# uradmonitor_D_100_61.net
KiCad netlist of a schematic drawn in EAGLE
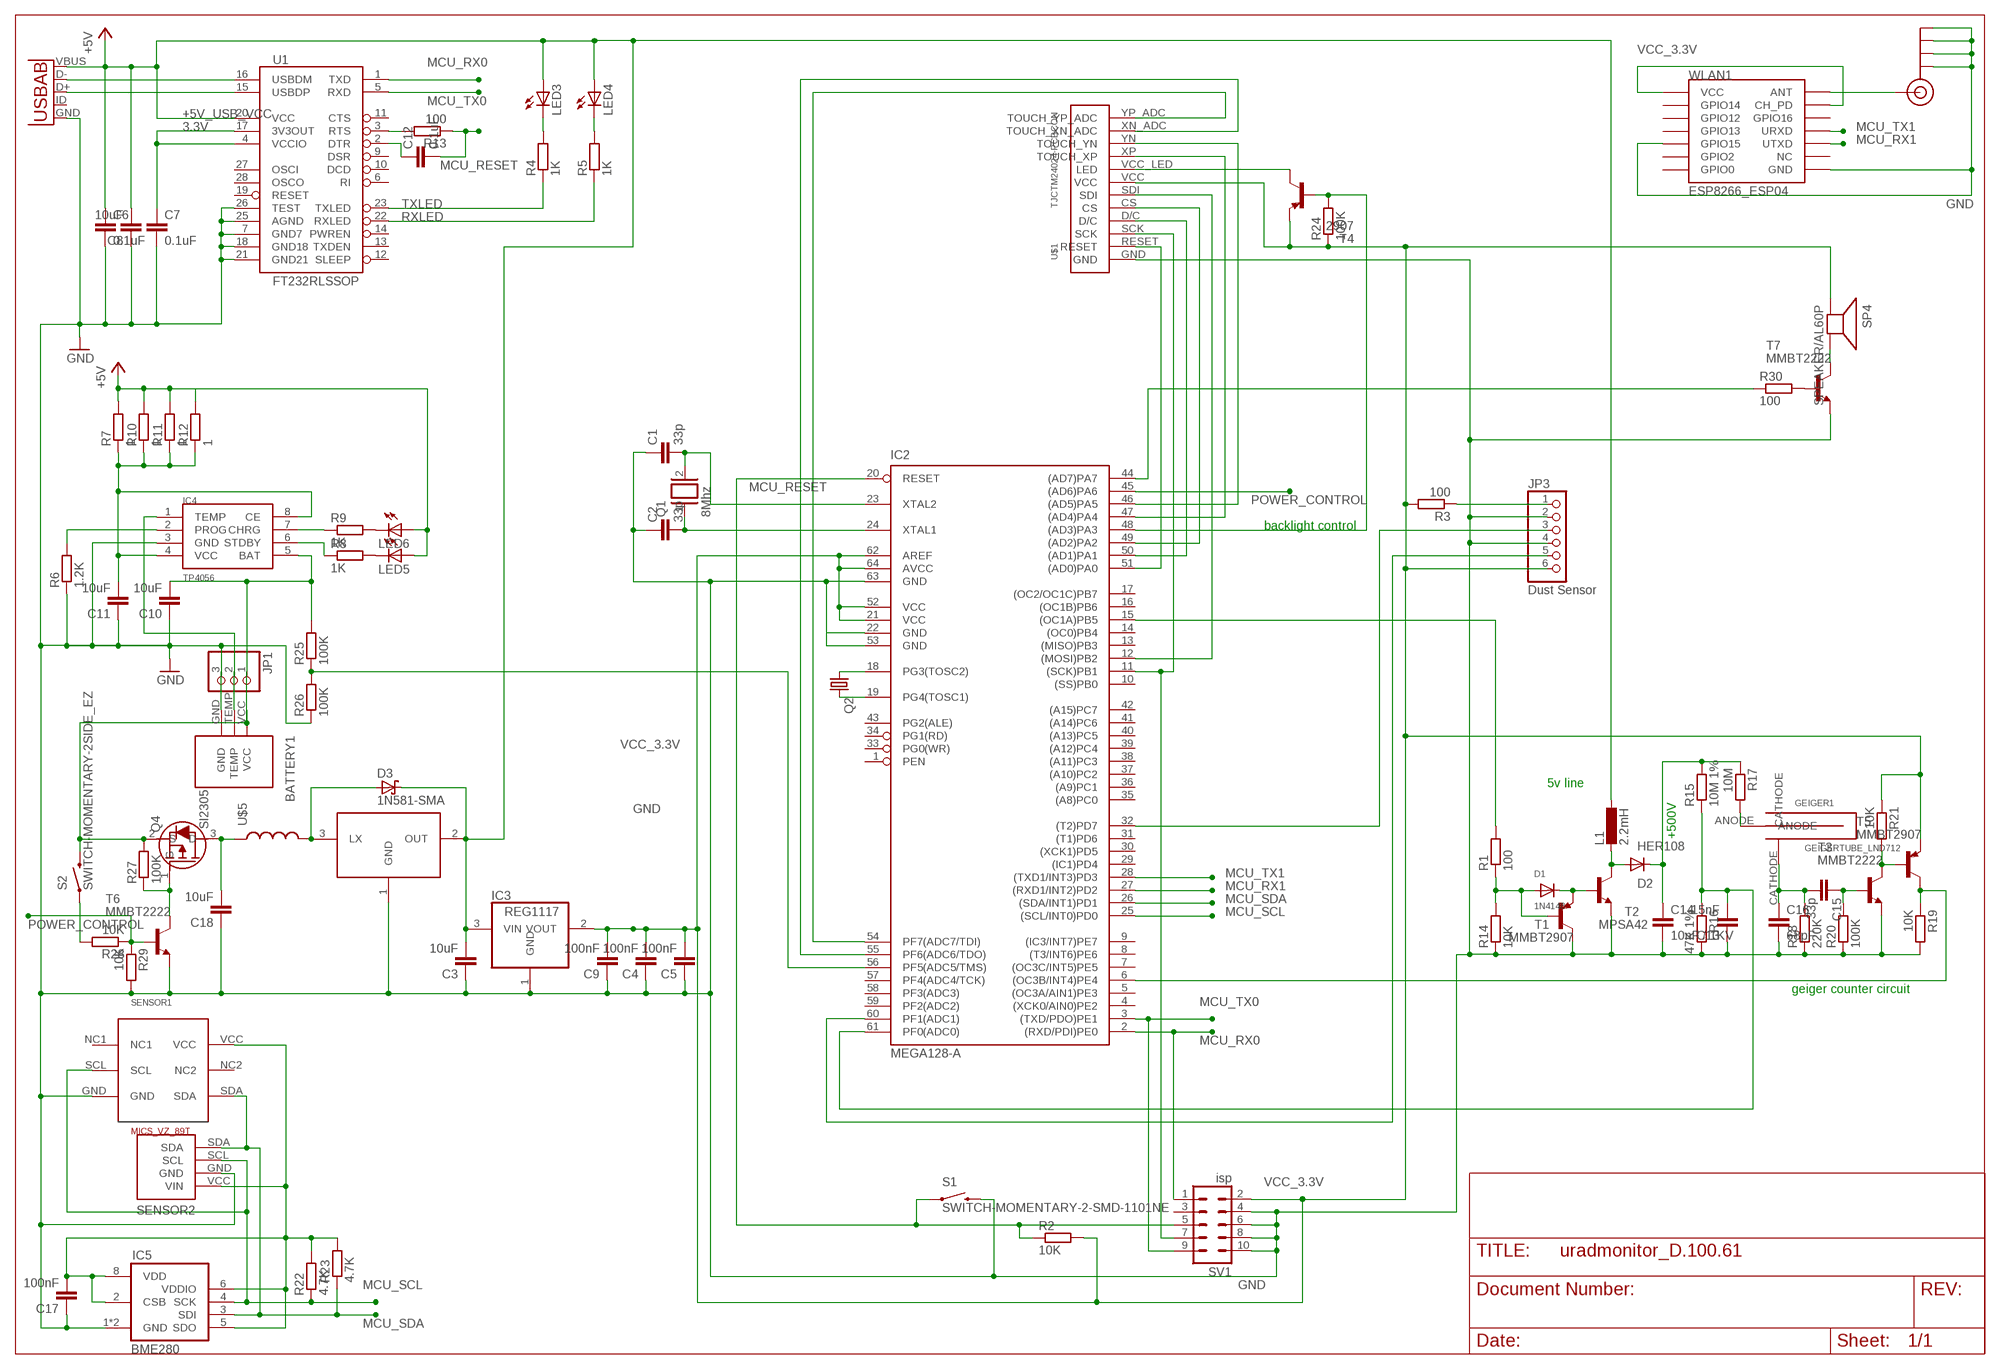
[diagram p0: schematic, sheet 1]

(export (version "E")
  (design (tool "Eeschema 10.0.6"))
  (components
    (comp (ref "BATTERY1")
      (value "BAT-CASIO-NP40BATTERY")
      (footprint "eagle-import:BAT-CASIO-NP40")
      (libsource (lib "eagle-import") (part "BAT-CASIO-NP40BATTERY"))
    )
    (comp (ref "C1")
      (value "33p")
      (footprint "eagle-import:C0805K")
      (libsource (lib "eagle-import") (part "C-EUC0805K"))
    )
    (comp (ref "C2")
      (value "33p")
      (footprint "eagle-import:C0805K")
      (libsource (lib "eagle-import") (part "C-EUC0805K"))
    )
    (comp (ref "C3")
      (value "10uF")
      (footprint "eagle-import:C0805K")
      (libsource (lib "eagle-import") (part "C-EUC0805K"))
    )
    (comp (ref "C4")
      (value "100nF")
      (footprint "eagle-import:C0805K")
      (libsource (lib "eagle-import") (part "C-EUC0805K"))
    )
    (comp (ref "C5")
      (value "100nF")
      (footprint "eagle-import:C0805K")
      (libsource (lib "eagle-import") (part "C-EUC0805K"))
    )
    (comp (ref "C6")
      (value "0.1uF")
      (footprint "eagle-import:0805")
      (libsource (lib "eagle-import") (part "CAP0805"))
    )
    (comp (ref "C7")
      (value "0.1uF")
      (footprint "eagle-import:0805")
      (libsource (lib "eagle-import") (part "CAP0805"))
    )
    (comp (ref "C8")
      (value "10uF")
      (footprint "eagle-import:C0805K")
      (libsource (lib "eagle-import") (part "C-EUC0805K"))
    )
    (comp (ref "C9")
      (value "100nF")
      (footprint "eagle-import:C0805K")
      (libsource (lib "eagle-import") (part "C-EUC0805K"))
    )
    (comp (ref "C10")
      (value "10uF")
      (footprint "eagle-import:C0805K")
      (libsource (lib "eagle-import") (part "C-EUC0805K"))
    )
    (comp (ref "C11")
      (value "10uF")
      (footprint "eagle-import:C0805K")
      (libsource (lib "eagle-import") (part "C-EUC0805K"))
    )
    (comp (ref "C12")
      (value "0.1uF")
      (footprint "eagle-import:0805")
      (libsource (lib "eagle-import") (part "CAP0805"))
    )
    (comp (ref "C13")
      (value "15nF")
      (footprint "eagle-import:C0805K")
      (libsource (lib "eagle-import") (part "C-EUC0805K"))
    )
    (comp (ref "C14")
      (value "10nF / 1KV")
      (footprint "eagle-import:C050-025X075")
      (libsource (lib "eagle-import") (part "C-EU050-025X075"))
    )
    (comp (ref "C15")
      (value "33p")
      (footprint "eagle-import:C0805K")
      (libsource (lib "eagle-import") (part "C-EUC0805K"))
    )
    (comp (ref "C16")
      (value "68pF")
      (footprint "eagle-import:C0805K")
      (libsource (lib "eagle-import") (part "C-EUC0805K"))
    )
    (comp (ref "C17")
      (value "100nF")
      (footprint "eagle-import:C0805K")
      (libsource (lib "eagle-import") (part "C-EUC0805K"))
    )
    (comp (ref "C18")
      (value "10uF")
      (footprint "eagle-import:C0805K")
      (libsource (lib "eagle-import") (part "C-EUC0805K"))
    )
    (comp (ref "D1")
      (value "1N4148")
      (footprint "eagle-import:SOD-323F")
      (libsource (lib "eagle-import") (part "DIODESOD-323F"))
    )
    (comp (ref "D2")
      (value "HER108")
      (footprint "eagle-import:DO-214AC")
      (libsource (lib "eagle-import") (part "DIODE-DO-214AC"))
    )
    (comp (ref "D3")
      (value "1N581-SMA")
      (footprint "eagle-import:SMA-DIODE")
      (libsource (lib "eagle-import") (part "1N581-SMA"))
    )
    (comp (ref "GEIGER1")
      (value "GEIGERTUBE_LND712")
      (footprint "eagle-import:GEIGERTUBE_LND712")
      (libsource (lib "eagle-import") (part "GEIGERTUBE_LND712"))
    )
    (comp (ref "IC2")
      (value "MEGA128-A")
      (footprint "eagle-import:TQFP64")
      (fields (field (name "MPN") "ATMEGA128-16AU"))
      (libsource (lib "eagle-import") (part "MEGA128-A"))
    )
    (comp (ref "IC3")
      (value "REG1117")
      (footprint "eagle-import:SOT223")
      (libsource (lib "eagle-import") (part "REG1117"))
    )
    (comp (ref "IC4")
      (value "TP4056")
      (footprint "eagle-import:TP4056")
      (libsource (lib "eagle-import") (part "TP4056"))
    )
    (comp (ref "IC5")
      (value "BME280")
      (footprint "eagle-import:BME280")
      (libsource (lib "eagle-import") (part "BME280"))
    )
    (comp (ref "J$1")
      (value "SMA_EDGE")
      (footprint "eagle-import:SMA-EDGE")
      (libsource (lib "eagle-import") (part "SMA_EDGE"))
    )
    (comp (ref "JP1")
      (value "PINHD-1X3")
      (footprint "eagle-import:1X03")
      (libsource (lib "eagle-import") (part "PINHD-1X3"))
    )
    (comp (ref "JP3")
      (value "Dust Sensor")
      (footprint "eagle-import:1X06-CLEANBIG")
      (libsource (lib "eagle-import") (part "PINHD-1X6CB"))
    )
    (comp (ref "L1")
      (value "2.2mH")
      (footprint "eagle-import:L1812")
      (libsource (lib "eagle-import") (part "L-EUL1812"))
    )
    (comp (ref "LED3")
      (value "LEDCHIP-LED0805")
      (footprint "eagle-import:CHIP-LED0805")
      (libsource (lib "eagle-import") (part "LEDCHIP-LED0805"))
    )
    (comp (ref "LED4")
      (value "LEDCHIP-LED0805")
      (footprint "eagle-import:CHIP-LED0805")
      (libsource (lib "eagle-import") (part "LEDCHIP-LED0805"))
    )
    (comp (ref "LED5")
      (value "LED3MM")
      (footprint "eagle-import:LED3MM")
      (libsource (lib "eagle-import") (part "LED3MM"))
    )
    (comp (ref "LED6")
      (value "LED3MM")
      (footprint "eagle-import:LED3MM")
      (libsource (lib "eagle-import") (part "LED3MM"))
    )
    (comp (ref "Q1")
      (value "8Mhz")
      (footprint "eagle-import:QS")
      (libsource (lib "eagle-import") (part "XTAL/S"))
    )
    (comp (ref "Q2")
      (value "CRYSTALTC26H")
      (footprint "eagle-import:TC26H")
      (libsource (lib "eagle-import") (part "CRYSTALTC26H"))
    )
    (comp (ref "Q4")
      (value "SI2305")
      (footprint "eagle-import:SOT23")
      (libsource (lib "eagle-import") (part "SI2305"))
    )
    (comp (ref "R1")
      (value "100")
      (footprint "eagle-import:R0805")
      (libsource (lib "eagle-import") (part "resistor_R-EU_R0805"))
    )
    (comp (ref "R2")
      (value "10K")
      (footprint "eagle-import:R0805")
      (libsource (lib "eagle-import") (part "R-EU_R0805"))
    )
    (comp (ref "R3")
      (value "100")
      (footprint "eagle-import:R0805")
      (libsource (lib "eagle-import") (part "resistor_R-EU_R0805"))
    )
    (comp (ref "R4")
      (value "1K")
      (footprint "eagle-import:R0805")
      (libsource (lib "eagle-import") (part "R-EU_R0805"))
    )
    (comp (ref "R5")
      (value "1K")
      (footprint "eagle-import:R0805")
      (libsource (lib "eagle-import") (part "R-EU_R0805"))
    )
    (comp (ref "R6")
      (value "1.2K")
      (footprint "eagle-import:R0805")
      (libsource (lib "eagle-import") (part "R-EU_R0805"))
    )
    (comp (ref "R7")
      (value "1")
      (footprint "eagle-import:R0805")
      (libsource (lib "eagle-import") (part "R-EU_R0805"))
    )
    (comp (ref "R8")
      (value "1K")
      (footprint "eagle-import:R0805")
      (libsource (lib "eagle-import") (part "R-EU_R0805"))
    )
    (comp (ref "R9")
      (value "1K")
      (footprint "eagle-import:R0805")
      (libsource (lib "eagle-import") (part "R-EU_R0805"))
    )
    (comp (ref "R10")
      (value "1")
      (footprint "eagle-import:R0805")
      (libsource (lib "eagle-import") (part "R-EU_R0805"))
    )
    (comp (ref "R11")
      (value "1")
      (footprint "eagle-import:R0805")
      (libsource (lib "eagle-import") (part "R-EU_R0805"))
    )
    (comp (ref "R12")
      (value "1")
      (footprint "eagle-import:R0805")
      (libsource (lib "eagle-import") (part "R-EU_R0805"))
    )
    (comp (ref "R13")
      (value "100")
      (footprint "eagle-import:R0805")
      (libsource (lib "eagle-import") (part "R-EU_R0805"))
    )
    (comp (ref "R14")
      (value "10K")
      (footprint "eagle-import:R0805")
      (libsource (lib "eagle-import") (part "resistor_R-EU_R0805"))
    )
    (comp (ref "R15")
      (value "10M 1%")
      (footprint "eagle-import:0204_7")
      (libsource (lib "eagle-import") (part "R-EU_0204/7"))
    )
    (comp (ref "R16")
      (value "47K 1%")
      (footprint "eagle-import:R0805")
      (libsource (lib "eagle-import") (part "R-EU_R0805"))
    )
    (comp (ref "R17")
      (value "10M")
      (footprint "eagle-import:0204_7")
      (libsource (lib "eagle-import") (part "R-EU_0204/7"))
    )
    (comp (ref "R18")
      (value "220K")
      (footprint "eagle-import:0204_7")
      (libsource (lib "eagle-import") (part "R-EU_0204/7"))
    )
    (comp (ref "R19")
      (value "10K")
      (footprint "eagle-import:R0805")
      (libsource (lib "eagle-import") (part "R-EU_R0805"))
    )
    (comp (ref "R20")
      (value "100K")
      (footprint "eagle-import:R0805")
      (libsource (lib "eagle-import") (part "R-EU_R0805"))
    )
    (comp (ref "R21")
      (value "10K")
      (footprint "eagle-import:R0805")
      (libsource (lib "eagle-import") (part "R-EU_R0805"))
    )
    (comp (ref "R22")
      (value "4.7K")
      (footprint "eagle-import:R0805")
      (libsource (lib "eagle-import") (part "R-EU_R0805"))
    )
    (comp (ref "R23")
      (value "4.7K")
      (footprint "eagle-import:R0805")
      (libsource (lib "eagle-import") (part "R-EU_R0805"))
    )
    (comp (ref "R24")
      (value "100K")
      (footprint "eagle-import:R0805")
      (libsource (lib "eagle-import") (part "resistor_R-EU_R0805"))
    )
    (comp (ref "R25")
      (value "100K")
      (footprint "eagle-import:R0805")
      (libsource (lib "eagle-import") (part "R-EU_R0805"))
    )
    (comp (ref "R26")
      (value "100K")
      (footprint "eagle-import:R0805")
      (libsource (lib "eagle-import") (part "R-EU_R0805"))
    )
    (comp (ref "R27")
      (value "100K")
      (footprint "eagle-import:R0805")
      (libsource (lib "eagle-import") (part "R-EU_R0805"))
    )
    (comp (ref "R28")
      (value "10K")
      (footprint "eagle-import:R0805")
      (libsource (lib "eagle-import") (part "R-EU_R0805"))
    )
    (comp (ref "R29")
      (value "10K")
      (footprint "eagle-import:R0805")
      (libsource (lib "eagle-import") (part "R-EU_R0805"))
    )
    (comp (ref "R30")
      (value "100")
      (footprint "eagle-import:R0805")
      (libsource (lib "eagle-import") (part "R-EU_R0805"))
    )
    (comp (ref "S1")
      (value "SWITCH-MOMENTARY-2-SMD-1101NE")
      (footprint "eagle-import:TACTILE-SWITCH-1101NE")
      (libsource (lib "eagle-import") (part "SWITCH-MOMENTARY-2-SMD-1101NE"))
    )
    (comp (ref "S2")
      (value "SWITCH-MOMENTARY-2SIDE_EZ")
      (footprint "eagle-import:TACTILE-PTH-SIDEEZ")
      (libsource (lib "eagle-import") (part "SWITCH-MOMENTARY-2SIDE_EZ"))
    )
    (comp (ref "SENSOR1")
      (value "MICS_VZ_89T")
      (footprint "eagle-import:MICS_VZ_89T")
      (libsource (lib "eagle-import") (part "MICS_VZ_89T"))
    )
    (comp (ref "SENSOR2")
      (value "SENSOR_GY68GY-86DIP")
      (footprint "eagle-import:SENSOR_GY68")
      (libsource (lib "eagle-import") (part "SENSOR_GY68GY-86DIP"))
    )
    (comp (ref "SP4")
      (value "SPEAKER/AL60P")
      (footprint "eagle-import:AL60P")
      (libsource (lib "eagle-import") (part "SPEAKER/AL60P"))
    )
    (comp (ref "SV1")
      (value "isp")
      (footprint "eagle-import:MA05-2")
      (libsource (lib "eagle-import") (part "MA05-2"))
    )
    (comp (ref "T1")
      (value "MMBT2907")
      (footprint "eagle-import:SOT23-BEC")
      (libsource (lib "eagle-import") (part "-PNP-SOT23-BECMMBT2907ALT1"))
    )
    (comp (ref "T2")
      (value "MPSA42")
      (footprint "eagle-import:SOT23-BEC")
      (libsource (lib "eagle-import") (part "transistor-neu-to92_-NPN-SOT23-BECMMBTA42LT1"))
    )
    (comp (ref "T3")
      (value "MMBT2222")
      (footprint "eagle-import:SOT23-BEC")
      (libsource (lib "eagle-import") (part "transistor-neu-to92_-NPN-SOT23-BECMMBT2222ALT1"))
    )
    (comp (ref "T4")
      (value "2907")
      (footprint "eagle-import:SOT23-BEC")
      (libsource (lib "eagle-import") (part "-PNP-SOT23-BECMMBT2907ALT1"))
    )
    (comp (ref "T5")
      (value "MMBT2907")
      (footprint "eagle-import:SOT23-BEC")
      (libsource (lib "eagle-import") (part "-PNP-SOT23-BECMMBT2907ALT1"))
    )
    (comp (ref "T6")
      (value "MMBT2222")
      (footprint "eagle-import:SOT23-BEC")
      (libsource (lib "eagle-import") (part "-NPN-SOT23-BECMMBT2222ALT1"))
    )
    (comp (ref "T7")
      (value "MMBT2222")
      (footprint "eagle-import:SOT23-BEC")
      (libsource (lib "eagle-import") (part "-NPN-SOT23-BECMMBT2222ALT1"))
    )
    (comp (ref "U$1")
      (value "TJCTM24024-PCBCON")
      (footprint "eagle-import:TJCTM24024-PCBCON")
      (libsource (lib "eagle-import") (part "TJCTM24024-PCBCON"))
    )
    (comp (ref "U$2")
      (value "USB_AB")
      (footprint "eagle-import:USB-AB-MICRO-SMD")
      (libsource (lib "eagle-import") (part "USB_AB"))
    )
    (comp (ref "U$3")
      (value "BL8530-SOT89-3")
      (footprint "eagle-import:SOT-89-3")
      (libsource (lib "eagle-import") (part "BL8530-SOT89-3"))
    )
    (comp (ref "U$5")
      (value "INDUCTOR-B82462G")
      (footprint "eagle-import:B82462G")
      (libsource (lib "eagle-import") (part "INDUCTOR-B82462G"))
    )
    (comp (ref "U1")
      (value "FT232RLSSOP")
      (footprint "eagle-import:SSOP28DB")
      (libsource (lib "eagle-import") (part "FT232RLSSOP"))
    )
    (comp (ref "WLAN1")
      (value "ESP8266_ESP04")
      (footprint "eagle-import:ESP8266_ESP04")
      (libsource (lib "eagle-import") (part "ESP8266_ESP04"))
    )
  )
  (nets
    (net (code "1") (name "+5V") (class "Default")
      (node (ref "C3") (pin "2") (pinfunction "2_2") (pintype "passive"))
      (node (ref "C6") (pin "1") (pinfunction "1_1") (pintype "passive"))
      (node (ref "C8") (pin "2") (pinfunction "2_2") (pintype "passive"))
      (node (ref "D3") (pin "C") (pinfunction "C_C") (pintype "passive"))
      (node (ref "IC3") (pin "3") (pinfunction "VIN_3") (pintype "input"))
      (node (ref "L1") (pin "1") (pinfunction "1_1") (pintype "passive"))
      (node (ref "LED3") (pin "A") (pinfunction "A_A") (pintype "passive"))
      (node (ref "LED4") (pin "A") (pinfunction "A_A") (pintype "passive"))
      (node (ref "LED5") (pin "A") (pinfunction "A_A") (pintype "passive"))
      (node (ref "LED6") (pin "A") (pinfunction "A_A") (pintype "passive"))
      (node (ref "R10") (pin "2") (pinfunction "2_2") (pintype "passive"))
      (node (ref "R11") (pin "2") (pinfunction "2_2") (pintype "passive"))
      (node (ref "R12") (pin "2") (pinfunction "2_2") (pintype "passive"))
      (node (ref "R7") (pin "2") (pinfunction "2_2") (pintype "passive"))
      (node (ref "U$2") (pin "VBUS") (pinfunction "VBUS_VBUS") (pintype "bidirectional"))
      (node (ref "U$3") (pin "2") (pinfunction "OUT_2") (pintype "bidirectional"))
      (node (ref "U1") (pin "20") (pinfunction "VCC_20") (pintype "power_in"))
    )
    (net (code "2") (name "/3.3V") (class "Default")
      (node (ref "C7") (pin "1") (pinfunction "1_1") (pintype "passive"))
      (node (ref "U1") (pin "17") (pinfunction "3V3OUT_17") (pintype "output"))
      (node (ref "U1") (pin "4") (pinfunction "VCCIO_4") (pintype "power_in"))
    )
    (net (code "3") (name "/MCU_RESET") (class "Default")
      (node (ref "C12") (pin "2") (pinfunction "2_2") (pintype "passive"))
      (node (ref "IC2") (pin "20") (pinfunction "RESET_20") (pintype "input"))
      (node (ref "R13") (pin "1") (pinfunction "1_1") (pintype "passive"))
      (node (ref "R2") (pin "1") (pinfunction "1_1") (pintype "passive"))
      (node (ref "S1") (pin "P$1") (pinfunction "1_P$1") (pintype "passive"))
      (node (ref "SV1") (pin "5") (pinfunction "5_5") (pintype "passive"))
    )
    (net (code "4") (name "/MCU_RX0") (class "Default")
      (node (ref "IC2") (pin "2") (pinfunction "(RXD/PDI)PE0_2") (pintype "bidirectional"))
      (node (ref "SV1") (pin "1") (pinfunction "1_1") (pintype "passive"))
      (node (ref "U1") (pin "1") (pinfunction "TXD_1") (pintype "output"))
    )
    (net (code "5") (name "/MCU_RX1") (class "Default")
      (node (ref "IC2") (pin "27") (pinfunction "(RXD1/INT2)PD2_27") (pintype "bidirectional"))
      (node (ref "WLAN1") (pin "UTXD") (pinfunction "UTXD_UTXD") (pintype "bidirectional"))
    )
    (net (code "6") (name "/MCU_SCL") (class "Default")
      (node (ref "IC2") (pin "25") (pinfunction "(SCL/INT0)PD0_25") (pintype "bidirectional"))
      (node (ref "IC5") (pin "4") (pinfunction "SCK_4") (pintype "bidirectional"))
      (node (ref "R22") (pin "1") (pinfunction "1_1") (pintype "passive"))
      (node (ref "SENSOR1") (pin "SCL") (pinfunction "SCL_SCL") (pintype "bidirectional"))
      (node (ref "SENSOR2") (pin "SCL") (pinfunction "SCL_SCL") (pintype "bidirectional"))
    )
    (net (code "7") (name "/MCU_SDA") (class "Default")
      (node (ref "IC2") (pin "26") (pinfunction "(SDA/INT1)PD1_26") (pintype "bidirectional"))
      (node (ref "IC5") (pin "3") (pinfunction "SDI_3") (pintype "bidirectional"))
      (node (ref "R23") (pin "1") (pinfunction "1_1") (pintype "passive"))
      (node (ref "SENSOR1") (pin "SDA") (pinfunction "SDA_SDA") (pintype "bidirectional"))
      (node (ref "SENSOR2") (pin "SDA") (pinfunction "SDA_SDA") (pintype "bidirectional"))
    )
    (net (code "8") (name "/MCU_TX0") (class "Default")
      (node (ref "IC2") (pin "3") (pinfunction "(TXD/PDO)PE1_3") (pintype "bidirectional"))
      (node (ref "SV1") (pin "9") (pinfunction "9_9") (pintype "passive"))
      (node (ref "U1") (pin "5") (pinfunction "RXD_5") (pintype "input"))
    )
    (net (code "9") (name "/MCU_TX1") (class "Default")
      (node (ref "IC2") (pin "28") (pinfunction "(TXD1/INT3)PD3_28") (pintype "bidirectional"))
      (node (ref "WLAN1") (pin "URXD") (pinfunction "URXD_URXD") (pintype "bidirectional"))
    )
    (net (code "10") (name "/POWER_CONTROL") (class "Default")
      (node (ref "IC2") (pin "45") (pinfunction "(AD6)PA6_45") (pintype "bidirectional"))
      (node (ref "R28") (pin "1") (pinfunction "1_1") (pintype "passive"))
      (node (ref "R29") (pin "1") (pinfunction "1_1") (pintype "passive"))
      (node (ref "T6") (pin "B") (pinfunction "B_B") (pintype "passive"))
    )
    (net (code "11") (name "/RXLED") (class "Default")
      (node (ref "R5") (pin "1") (pinfunction "1_1") (pintype "passive"))
      (node (ref "U1") (pin "22") (pinfunction "RXLED_22") (pintype "input"))
    )
    (net (code "12") (name "/TXLED") (class "Default")
      (node (ref "R4") (pin "1") (pinfunction "1_1") (pintype "passive"))
      (node (ref "U1") (pin "23") (pinfunction "TXLED_23") (pintype "input"))
    )
    (net (code "13") (name "/VCC_3.3V") (class "Default")
      (node (ref "C17") (pin "2") (pinfunction "2_2") (pintype "passive"))
      (node (ref "C4") (pin "2") (pinfunction "2_2") (pintype "passive"))
      (node (ref "C5") (pin "2") (pinfunction "2_2") (pintype "passive"))
      (node (ref "C9") (pin "2") (pinfunction "2_2") (pintype "passive"))
      (node (ref "IC2") (pin "21") (pinfunction "VCC_21") (pintype "power_in"))
      (node (ref "IC2") (pin "52") (pinfunction "VCC_52") (pintype "power_in"))
      (node (ref "IC2") (pin "62") (pinfunction "AREF_62") (pintype "passive"))
      (node (ref "IC2") (pin "64") (pinfunction "AVCC_64") (pintype "power_in"))
      (node (ref "IC3") (pin "2") (pinfunction "VOUT_2") (pintype "output"))
      (node (ref "IC5") (pin "2") (pinfunction "CSB_2") (pintype "input"))
      (node (ref "IC5") (pin "5") (pinfunction "SDO_5") (pintype "input"))
      (node (ref "IC5") (pin "6") (pinfunction "VDDIO_6") (pintype "power_in"))
      (node (ref "IC5") (pin "8") (pinfunction "VDD_8") (pintype "power_in"))
      (node (ref "JP3") (pin "6") (pinfunction "6_6") (pintype "passive"))
      (node (ref "R2") (pin "2") (pinfunction "2_2") (pintype "passive"))
      (node (ref "R21") (pin "1") (pinfunction "1_1") (pintype "passive"))
      (node (ref "R22") (pin "2") (pinfunction "2_2") (pintype "passive"))
      (node (ref "R23") (pin "2") (pinfunction "2_2") (pintype "passive"))
      (node (ref "R24") (pin "1") (pinfunction "1_1") (pintype "passive"))
      (node (ref "R3") (pin "2") (pinfunction "2_2") (pintype "passive"))
      (node (ref "SENSOR1") (pin "VCC") (pinfunction "VCC_VCC") (pintype "bidirectional"))
      (node (ref "SENSOR2") (pin "VCC") (pinfunction "VIN_VCC") (pintype "bidirectional"))
      (node (ref "SP4") (pin "1") (pinfunction "+_1") (pintype "passive"))
      (node (ref "SV1") (pin "2") (pinfunction "2_2") (pintype "passive"))
      (node (ref "T4") (pin "E") (pinfunction "E_E") (pintype "passive"))
      (node (ref "T5") (pin "E") (pinfunction "E_E") (pintype "passive"))
      (node (ref "U$1") (pin "VCC") (pinfunction "VCC_VCC") (pintype "bidirectional"))
      (node (ref "WLAN1") (pin "CH_PD") (pinfunction "CH_PD_CH_PD") (pintype "bidirectional"))
      (node (ref "WLAN1") (pin "VCC") (pinfunction "VCC_VCC") (pintype "bidirectional"))
    )
    (net (code "14") (name "GND") (class "Default")
      (node (ref "BATTERY1") (pin "GND") (pinfunction "GND_GND") (pintype "bidirectional"))
      (node (ref "C1") (pin "1") (pinfunction "1_1") (pintype "passive"))
      (node (ref "C10") (pin "1") (pinfunction "1_1") (pintype "passive"))
      (node (ref "C11") (pin "1") (pinfunction "1_1") (pintype "passive"))
      (node (ref "C13") (pin "1") (pinfunction "1_1") (pintype "passive"))
      (node (ref "C14") (pin "2") (pinfunction "2_2") (pintype "passive"))
      (node (ref "C16") (pin "2") (pinfunction "2_2") (pintype "passive"))
      (node (ref "C17") (pin "1") (pinfunction "1_1") (pintype "passive"))
      (node (ref "C18") (pin "1") (pinfunction "1_1") (pintype "passive"))
      (node (ref "C2") (pin "1") (pinfunction "1_1") (pintype "passive"))
      (node (ref "C3") (pin "1") (pinfunction "1_1") (pintype "passive"))
      (node (ref "C4") (pin "1") (pinfunction "1_1") (pintype "passive"))
      (node (ref "C5") (pin "1") (pinfunction "1_1") (pintype "passive"))
      (node (ref "C6") (pin "2") (pinfunction "2_2") (pintype "passive"))
      (node (ref "C7") (pin "2") (pinfunction "2_2") (pintype "passive"))
      (node (ref "C8") (pin "1") (pinfunction "1_1") (pintype "passive"))
      (node (ref "C9") (pin "1") (pinfunction "1_1") (pintype "passive"))
      (node (ref "IC2") (pin "22") (pinfunction "GND_22") (pintype "power_in"))
      (node (ref "IC2") (pin "53") (pinfunction "GND_53") (pintype "power_in"))
      (node (ref "IC2") (pin "63") (pinfunction "GND_63") (pintype "power_in"))
      (node (ref "IC3") (pin "1") (pinfunction "GND_1") (pintype "power_in"))
      (node (ref "IC4") (pin "3") (pinfunction "GND_3") (pintype "bidirectional"))
      (node (ref "IC5") (pin "1") (pinfunction "GND_1") (pintype "power_in"))
      (node (ref "IC5") (pin "7") (pinfunction "GND_7") (pintype "power_in"))
      (node (ref "J$1") (pin "GND@0") (pinfunction "GND_GND@0") (pintype "bidirectional"))
      (node (ref "J$1") (pin "GND@1") (pinfunction "GND_GND@1") (pintype "bidirectional"))
      (node (ref "J$1") (pin "GND@2") (pinfunction "GND_GND@2") (pintype "bidirectional"))
      (node (ref "J$1") (pin "GND@3") (pinfunction "GND_GND@3") (pintype "bidirectional"))
      (node (ref "JP1") (pin "3") (pinfunction "3_3") (pintype "passive"))
      (node (ref "JP3") (pin "2") (pinfunction "2_2") (pintype "passive"))
      (node (ref "JP3") (pin "4") (pinfunction "4_4") (pintype "passive"))
      (node (ref "R14") (pin "1") (pinfunction "1_1") (pintype "passive"))
      (node (ref "R16") (pin "2") (pinfunction "2_2") (pintype "passive"))
      (node (ref "R18") (pin "1") (pinfunction "1_1") (pintype "passive"))
      (node (ref "R19") (pin "2") (pinfunction "2_2") (pintype "passive"))
      (node (ref "R20") (pin "1") (pinfunction "1_1") (pintype "passive"))
      (node (ref "R26") (pin "1") (pinfunction "1_1") (pintype "passive"))
      (node (ref "R29") (pin "2") (pinfunction "2_2") (pintype "passive"))
      (node (ref "R6") (pin "1") (pinfunction "1_1") (pintype "passive"))
      (node (ref "S1") (pin "P$2") (pinfunction "2_P$2") (pintype "passive"))
      (node (ref "SENSOR1") (pin "GND") (pinfunction "GND_GND") (pintype "bidirectional"))
      (node (ref "SENSOR2") (pin "GND") (pinfunction "GND_GND") (pintype "bidirectional"))
      (node (ref "SV1") (pin "10") (pinfunction "10_10") (pintype "passive"))
      (node (ref "SV1") (pin "4") (pinfunction "4_4") (pintype "passive"))
      (node (ref "SV1") (pin "6") (pinfunction "6_6") (pintype "passive"))
      (node (ref "SV1") (pin "8") (pinfunction "8_8") (pintype "passive"))
      (node (ref "T1") (pin "C") (pinfunction "C_C") (pintype "passive"))
      (node (ref "T2") (pin "E") (pinfunction "E_E") (pintype "passive"))
      (node (ref "T3") (pin "E") (pinfunction "E_E") (pintype "passive"))
      (node (ref "T6") (pin "E") (pinfunction "E_E") (pintype "passive"))
      (node (ref "T7") (pin "E") (pinfunction "E_E") (pintype "passive"))
      (node (ref "U$1") (pin "GND") (pinfunction "GND_GND") (pintype "bidirectional"))
      (node (ref "U$2") (pin "GND") (pinfunction "GND_GND") (pintype "bidirectional"))
      (node (ref "U$3") (pin "1") (pinfunction "GND_1") (pintype "bidirectional"))
      (node (ref "U1") (pin "18") (pinfunction "GND18_18") (pintype "power_in"))
      (node (ref "U1") (pin "21") (pinfunction "GND21_21") (pintype "power_in"))
      (node (ref "U1") (pin "25") (pinfunction "AGND_25") (pintype "power_in"))
      (node (ref "U1") (pin "26") (pinfunction "TEST_26") (pintype "input"))
      (node (ref "U1") (pin "7") (pinfunction "GND7_7") (pintype "power_in"))
      (node (ref "WLAN1") (pin "GND") (pinfunction "GND_GND") (pintype "bidirectional"))
      (node (ref "WLAN1") (pin "GPIO15") (pinfunction "GPIO15_GPIO15") (pintype "bidirectional"))
    )
    (net (code "15") (name "Net-(C14-Pad1)") (class "Default")
      (node (ref "C14") (pin "1") (pinfunction "1_1") (pintype "passive"))
      (node (ref "D2") (pin "C") (pinfunction "C_C") (pintype "passive"))
      (node (ref "R15") (pin "2") (pinfunction "2_2") (pintype "passive"))
      (node (ref "R17") (pin "1") (pinfunction "1_1") (pintype "passive"))
    )
    (net (code "16") (name "Net-(C15-Pad1)") (class "Default")
      (node (ref "C15") (pin "1") (pinfunction "1_1") (pintype "passive"))
      (node (ref "R20") (pin "2") (pinfunction "2_2") (pintype "passive"))
      (node (ref "T3") (pin "B") (pinfunction "B_B") (pintype "passive"))
    )
    (net (code "17") (name "Net-(C15-Pad2)") (class "Default")
      (node (ref "C15") (pin "2") (pinfunction "2_2") (pintype "passive"))
      (node (ref "C16") (pin "1") (pinfunction "1_1") (pintype "passive"))
      (node (ref "GEIGER1") (pin "CATHODE") (pinfunction "CATHODE_CATHODE") (pintype "bidirectional"))
      (node (ref "R18") (pin "2") (pinfunction "2_2") (pintype "passive"))
    )
    (net (code "18") (name "Net-(D1-PadA)") (class "Default")
      (node (ref "D1") (pin "A") (pinfunction "A_A") (pintype "passive"))
      (node (ref "R1") (pin "1") (pinfunction "1_1") (pintype "passive"))
      (node (ref "R14") (pin "2") (pinfunction "2_2") (pintype "passive"))
      (node (ref "T1") (pin "B") (pinfunction "B_B") (pintype "passive"))
    )
    (net (code "19") (name "Net-(D1-PadC)") (class "Default")
      (node (ref "D1") (pin "C") (pinfunction "C_C") (pintype "passive"))
      (node (ref "T1") (pin "E") (pinfunction "E_E") (pintype "passive"))
      (node (ref "T2") (pin "B") (pinfunction "B_B") (pintype "passive"))
    )
    (net (code "20") (name "Net-(D2-PadA)") (class "Default")
      (node (ref "D2") (pin "A") (pinfunction "A_A") (pintype "passive"))
      (node (ref "L1") (pin "2") (pinfunction "2_2") (pintype "passive"))
      (node (ref "T2") (pin "C") (pinfunction "C_C") (pintype "passive"))
    )
    (net (code "21") (name "Net-(GEIGER1-PadANODE)") (class "Default")
      (node (ref "GEIGER1") (pin "ANODE") (pinfunction "ANODE_ANODE") (pintype "bidirectional"))
      (node (ref "R17") (pin "2") (pinfunction "2_2") (pintype "passive"))
    )
    (net (code "22") (name "Net-(IC2-(AD0)PA0)") (class "Default")
      (node (ref "IC2") (pin "51") (pinfunction "(AD0)PA0_51") (pintype "bidirectional"))
      (node (ref "U$1") (pin "RESET") (pinfunction "RESET_RESET") (pintype "bidirectional"))
    )
    (net (code "23") (name "Net-(IC2-(AD1)PA1)") (class "Default")
      (node (ref "IC2") (pin "50") (pinfunction "(AD1)PA1_50") (pintype "bidirectional"))
      (node (ref "U$1") (pin "D/C") (pinfunction "D/C_D/C") (pintype "bidirectional"))
    )
    (net (code "24") (name "Net-(IC2-(AD2)PA2)") (class "Default")
      (node (ref "IC2") (pin "49") (pinfunction "(AD2)PA2_49") (pintype "bidirectional"))
      (node (ref "U$1") (pin "CS") (pinfunction "CS_CS") (pintype "bidirectional"))
    )
    (net (code "25") (name "Net-(IC2-(AD3)PA3)") (class "Default")
      (node (ref "IC2") (pin "48") (pinfunction "(AD3)PA3_48") (pintype "bidirectional"))
      (node (ref "R24") (pin "2") (pinfunction "2_2") (pintype "passive"))
      (node (ref "T4") (pin "B") (pinfunction "B_B") (pintype "passive"))
    )
    (net (code "26") (name "Net-(IC2-(AD4)PA4)") (class "Default")
      (node (ref "IC2") (pin "47") (pinfunction "(AD4)PA4_47") (pintype "bidirectional"))
      (node (ref "U$1") (pin "XP") (pinfunction "TOUCH_XP_XP") (pintype "bidirectional"))
    )
    (net (code "27") (name "Net-(IC2-(AD5)PA5)") (class "Default")
      (node (ref "IC2") (pin "46") (pinfunction "(AD5)PA5_46") (pintype "bidirectional"))
      (node (ref "U$1") (pin "YN") (pinfunction "TOUCH_YN_YN") (pintype "bidirectional"))
    )
    (net (code "28") (name "Net-(IC2-(AD7)PA7)") (class "Default")
      (node (ref "IC2") (pin "44") (pinfunction "(AD7)PA7_44") (pintype "bidirectional"))
      (node (ref "R30") (pin "1") (pinfunction "1_1") (pintype "passive"))
    )
    (net (code "29") (name "Net-(IC2-(MOSI)PB2)") (class "Default")
      (node (ref "IC2") (pin "12") (pinfunction "(MOSI)PB2_12") (pintype "bidirectional"))
      (node (ref "U$1") (pin "SDI") (pinfunction "SDI_SDI") (pintype "bidirectional"))
    )
    (net (code "30") (name "Net-(IC2-(OC1A)PB5)") (class "Default")
      (node (ref "IC2") (pin "15") (pinfunction "(OC1A)PB5_15") (pintype "bidirectional"))
      (node (ref "R1") (pin "2") (pinfunction "2_2") (pintype "passive"))
    )
    (net (code "31") (name "Net-(IC2-(OC3B{slash}INT4)PE4)") (class "Default")
      (node (ref "IC2") (pin "6") (pinfunction "(OC3B/INT4)PE4_6") (pintype "bidirectional"))
      (node (ref "R19") (pin "1") (pinfunction "1_1") (pintype "passive"))
      (node (ref "T5") (pin "C") (pinfunction "C_C") (pintype "passive"))
    )
    (net (code "32") (name "Net-(IC2-(SCK)PB1)") (class "Default")
      (node (ref "IC2") (pin "11") (pinfunction "(SCK)PB1_11") (pintype "bidirectional"))
      (node (ref "SV1") (pin "7") (pinfunction "7_7") (pintype "passive"))
      (node (ref "U$1") (pin "SCK") (pinfunction "SCK_SCK") (pintype "bidirectional"))
    )
    (net (code "33") (name "Net-(IC2-(T2)PD7)") (class "Default")
      (node (ref "IC2") (pin "32") (pinfunction "(T2)PD7_32") (pintype "bidirectional"))
      (node (ref "JP3") (pin "3") (pinfunction "3_3") (pintype "passive"))
    )
    (net (code "34") (name "Net-(IC2-PF0(ADC0))") (class "Default")
      (node (ref "C13") (pin "2") (pinfunction "2_2") (pintype "passive"))
      (node (ref "IC2") (pin "61") (pinfunction "PF0(ADC0)_61") (pintype "input"))
      (node (ref "R15") (pin "1") (pinfunction "1_1") (pintype "passive"))
      (node (ref "R16") (pin "1") (pinfunction "1_1") (pintype "passive"))
    )
    (net (code "35") (name "Net-(IC2-PF1(ADC1))") (class "Default")
      (node (ref "IC2") (pin "60") (pinfunction "PF1(ADC1)_60") (pintype "input"))
      (node (ref "JP3") (pin "5") (pinfunction "5_5") (pintype "passive"))
    )
    (net (code "36") (name "Net-(IC2-PF5(ADC5{slash}TMS))") (class "Default")
      (node (ref "IC2") (pin "56") (pinfunction "PF5(ADC5/TMS)_56") (pintype "input"))
      (node (ref "R25") (pin "1") (pinfunction "1_1") (pintype "passive"))
      (node (ref "R26") (pin "2") (pinfunction "2_2") (pintype "passive"))
    )
    (net (code "37") (name "Net-(IC2-PF6(ADC6{slash}TDO))") (class "Default")
      (node (ref "IC2") (pin "55") (pinfunction "PF6(ADC6/TDO)_55") (pintype "input"))
      (node (ref "U$1") (pin "XN_ADC") (pinfunction "TOUCH_XN_ADC_XN_ADC") (pintype "bidirectional"))
    )
    (net (code "38") (name "Net-(IC2-PF7(ADC7{slash}TDI))") (class "Default")
      (node (ref "IC2") (pin "54") (pinfunction "PF7(ADC7/TDI)_54") (pintype "input"))
      (node (ref "U$1") (pin "YP_ADC") (pinfunction "TOUCH_YP_ADC_YP_ADC") (pintype "bidirectional"))
    )
    (net (code "39") (name "Net-(IC2-PG3(TOSC2))") (class "Default")
      (node (ref "IC2") (pin "18") (pinfunction "PG3(TOSC2)_18") (pintype "bidirectional"))
      (node (ref "Q2") (pin "1") (pinfunction "1_1") (pintype "passive"))
    )
    (net (code "40") (name "Net-(IC2-PG4(TOSC1))") (class "Default")
      (node (ref "IC2") (pin "19") (pinfunction "PG4(TOSC1)_19") (pintype "bidirectional"))
      (node (ref "Q2") (pin "2") (pinfunction "2_2") (pintype "passive"))
    )
    (net (code "41") (name "Net-(IC2-XTAL1)") (class "Default")
      (node (ref "C2") (pin "2") (pinfunction "2_2") (pintype "passive"))
      (node (ref "IC2") (pin "24") (pinfunction "XTAL1_24") (pintype "bidirectional"))
      (node (ref "Q1") (pin "1") (pinfunction "1_1") (pintype "passive"))
    )
    (net (code "42") (name "Net-(IC2-XTAL2)") (class "Default")
      (node (ref "C1") (pin "2") (pinfunction "2_2") (pintype "passive"))
      (node (ref "IC2") (pin "23") (pinfunction "XTAL2_23") (pintype "bidirectional"))
      (node (ref "Q1") (pin "2") (pinfunction "2_2") (pintype "passive"))
    )
    (net (code "43") (name "Net-(IC4-BAT)") (class "Default")
      (node (ref "BATTERY1") (pin "VCC") (pinfunction "VCC_VCC") (pintype "bidirectional"))
      (node (ref "C10") (pin "2") (pinfunction "2_2") (pintype "passive"))
      (node (ref "IC4") (pin "5") (pinfunction "BAT_5") (pintype "bidirectional"))
      (node (ref "JP1") (pin "1") (pinfunction "1_1") (pintype "passive"))
      (node (ref "Q4") (pin "2") (pinfunction "S_2") (pintype "bidirectional"))
      (node (ref "R25") (pin "2") (pinfunction "2_2") (pintype "passive"))
      (node (ref "R27") (pin "2") (pinfunction "2_2") (pintype "passive"))
      (node (ref "S2") (pin "2") (pinfunction "2_2") (pintype "passive"))
    )
    (net (code "44") (name "Net-(IC4-CE)") (class "Default")
      (node (ref "C11") (pin "2") (pinfunction "2_2") (pintype "passive"))
      (node (ref "IC4") (pin "4") (pinfunction "VCC_4") (pintype "bidirectional"))
      (node (ref "IC4") (pin "8") (pinfunction "CE_8") (pintype "bidirectional"))
      (node (ref "R10") (pin "1") (pinfunction "1_1") (pintype "passive"))
      (node (ref "R11") (pin "1") (pinfunction "1_1") (pintype "passive"))
      (node (ref "R12") (pin "1") (pinfunction "1_1") (pintype "passive"))
      (node (ref "R7") (pin "1") (pinfunction "1_1") (pintype "passive"))
    )
    (net (code "45") (name "Net-(IC4-CHRG)") (class "Default")
      (node (ref "IC4") (pin "7") (pinfunction "CHRG_7") (pintype "bidirectional"))
      (node (ref "R9") (pin "1") (pinfunction "1_1") (pintype "passive"))
    )
    (net (code "46") (name "Net-(IC4-PROG)") (class "Default")
      (node (ref "IC4") (pin "2") (pinfunction "PROG_2") (pintype "bidirectional"))
      (node (ref "R6") (pin "2") (pinfunction "2_2") (pintype "passive"))
    )
    (net (code "47") (name "Net-(IC4-STDBY)") (class "Default")
      (node (ref "IC4") (pin "6") (pinfunction "STDBY_6") (pintype "bidirectional"))
      (node (ref "R8") (pin "1") (pinfunction "1_1") (pintype "passive"))
    )
    (net (code "48") (name "Net-(IC4-TEMP)") (class "Default")
      (node (ref "BATTERY1") (pin "TEMP") (pinfunction "TEMP_TEMP") (pintype "bidirectional"))
      (node (ref "IC4") (pin "1") (pinfunction "TEMP_1") (pintype "bidirectional"))
      (node (ref "JP1") (pin "2") (pinfunction "2_2") (pintype "passive"))
    )
    (net (code "49") (name "Net-(J$1-SIGNAL)") (class "Default")
      (node (ref "J$1") (pin "SIG") (pinfunction "SIGNAL_SIG") (pintype "bidirectional"))
      (node (ref "WLAN1") (pin "ANT") (pinfunction "ANT_ANT") (pintype "bidirectional"))
    )
    (net (code "50") (name "Net-(JP3-Pad1)") (class "Default")
      (node (ref "JP3") (pin "1") (pinfunction "1_1") (pintype "passive"))
      (node (ref "R3") (pin "1") (pinfunction "1_1") (pintype "passive"))
    )
    (net (code "51") (name "Net-(LED3-PadC)") (class "Default")
      (node (ref "LED3") (pin "C") (pinfunction "C_C") (pintype "passive"))
      (node (ref "R4") (pin "2") (pinfunction "2_2") (pintype "passive"))
    )
    (net (code "52") (name "Net-(LED4-PadC)") (class "Default")
      (node (ref "LED4") (pin "C") (pinfunction "C_C") (pintype "passive"))
      (node (ref "R5") (pin "2") (pinfunction "2_2") (pintype "passive"))
    )
    (net (code "53") (name "Net-(LED5-C)") (class "Default")
      (node (ref "LED5") (pin "K") (pinfunction "C_K") (pintype "passive"))
      (node (ref "R8") (pin "2") (pinfunction "2_2") (pintype "passive"))
    )
    (net (code "54") (name "Net-(LED6-C)") (class "Default")
      (node (ref "LED6") (pin "K") (pinfunction "C_K") (pintype "passive"))
      (node (ref "R9") (pin "2") (pinfunction "2_2") (pintype "passive"))
    )
    (net (code "55") (name "Net-(Q4-D)") (class "Default")
      (node (ref "C18") (pin "2") (pinfunction "2_2") (pintype "passive"))
      (node (ref "Q4") (pin "3") (pinfunction "D_3") (pintype "bidirectional"))
      (node (ref "U$5") (pin "P$1") (pinfunction "1_P$1") (pintype "passive"))
    )
    (net (code "56") (name "Net-(Q4-G)") (class "Default")
      (node (ref "Q4") (pin "1") (pinfunction "G_1") (pintype "bidirectional"))
      (node (ref "R27") (pin "1") (pinfunction "1_1") (pintype "passive"))
      (node (ref "T6") (pin "C") (pinfunction "C_C") (pintype "passive"))
    )
    (net (code "57") (name "Net-(R21-Pad2)") (class "Default")
      (node (ref "R21") (pin "2") (pinfunction "2_2") (pintype "passive"))
      (node (ref "T3") (pin "C") (pinfunction "C_C") (pintype "passive"))
      (node (ref "T5") (pin "B") (pinfunction "B_B") (pintype "passive"))
    )
    (net (code "58") (name "Net-(R28-Pad2)") (class "Default")
      (node (ref "R28") (pin "2") (pinfunction "2_2") (pintype "passive"))
      (node (ref "S2") (pin "1") (pinfunction "1_1") (pintype "passive"))
    )
    (net (code "59") (name "Net-(R30-Pad2)") (class "Default")
      (node (ref "R30") (pin "2") (pinfunction "2_2") (pintype "passive"))
      (node (ref "T7") (pin "B") (pinfunction "B_B") (pintype "passive"))
    )
    (net (code "60") (name "Net-(SP4--)") (class "Default")
      (node (ref "SP4") (pin "2") (pinfunction "-_2") (pintype "passive"))
      (node (ref "T7") (pin "C") (pinfunction "C_C") (pintype "passive"))
    )
    (net (code "61") (name "Net-(U$1-LED)") (class "Default")
      (node (ref "T4") (pin "C") (pinfunction "C_C") (pintype "passive"))
      (node (ref "U$1") (pin "VCC_LED") (pinfunction "LED_VCC_LED") (pintype "bidirectional"))
    )
    (net (code "62") (name "Net-(U$3-LX)") (class "Default")
      (node (ref "D3") (pin "A") (pinfunction "A_A") (pintype "passive"))
      (node (ref "U$3") (pin "3") (pinfunction "LX_3") (pintype "bidirectional"))
      (node (ref "U$5") (pin "P$2") (pinfunction "2_P$2") (pintype "passive"))
    )
    (net (code "63") (name "Net-(U1-DTR)") (class "Default")
      (node (ref "C12") (pin "1") (pinfunction "1_1") (pintype "passive"))
      (node (ref "U1") (pin "2") (pinfunction "DTR_2") (pintype "output"))
    )
    (net (code "64") (name "Net-(U1-RTS)") (class "Default")
      (node (ref "R13") (pin "2") (pinfunction "2_2") (pintype "passive"))
      (node (ref "U1") (pin "3") (pinfunction "RTS_3") (pintype "output"))
    )
    (net (code "65") (name "Net-(U1-USBDM)") (class "Default")
      (node (ref "U$2") (pin "D-") (pinfunction "D-_D-") (pintype "bidirectional"))
      (node (ref "U1") (pin "16") (pinfunction "USBDM_16") (pintype "bidirectional"))
    )
    (net (code "66") (name "Net-(U1-USBDP)") (class "Default")
      (node (ref "U$2") (pin "D+") (pinfunction "D+_D+") (pintype "bidirectional"))
      (node (ref "U1") (pin "15") (pinfunction "USBDP_15") (pintype "bidirectional"))
    )
    (net (code "67") (name "unconnected-(IC2-(A8)PC0-Pad35)") (class "Default")
      (node (ref "IC2") (pin "35") (pinfunction "(A8)PC0_35") (pintype "output"))
    )
    (net (code "68") (name "unconnected-(IC2-(A9)PC1-Pad36)") (class "Default")
      (node (ref "IC2") (pin "36") (pinfunction "(A9)PC1_36") (pintype "output"))
    )
    (net (code "69") (name "unconnected-(IC2-(A10)PC2-Pad37)") (class "Default")
      (node (ref "IC2") (pin "37") (pinfunction "(A10)PC2_37") (pintype "output"))
    )
    (net (code "70") (name "unconnected-(IC2-(A11)PC3-Pad38)") (class "Default")
      (node (ref "IC2") (pin "38") (pinfunction "(A11)PC3_38") (pintype "output"))
    )
    (net (code "71") (name "unconnected-(IC2-(A12)PC4-Pad39)") (class "Default")
      (node (ref "IC2") (pin "39") (pinfunction "(A12)PC4_39") (pintype "output"))
    )
    (net (code "72") (name "unconnected-(IC2-(A13)PC5-Pad40)") (class "Default")
      (node (ref "IC2") (pin "40") (pinfunction "(A13)PC5_40") (pintype "output"))
    )
    (net (code "73") (name "unconnected-(IC2-(A14)PC6-Pad41)") (class "Default")
      (node (ref "IC2") (pin "41") (pinfunction "(A14)PC6_41") (pintype "output"))
    )
    (net (code "74") (name "unconnected-(IC2-(A15)PC7-Pad42)") (class "Default")
      (node (ref "IC2") (pin "42") (pinfunction "(A15)PC7_42") (pintype "output"))
    )
    (net (code "75") (name "unconnected-(IC2-(IC1)PD4-Pad29)") (class "Default")
      (node (ref "IC2") (pin "29") (pinfunction "(IC1)PD4_29") (pintype "bidirectional"))
    )
    (net (code "76") (name "unconnected-(IC2-(IC3{slash}INT7)PE7-Pad9)") (class "Default")
      (node (ref "IC2") (pin "9") (pinfunction "(IC3/INT7)PE7_9") (pintype "bidirectional"))
    )
    (net (code "77") (name "unconnected-(IC2-(MISO)PB3-Pad13)") (class "Default")
      (node (ref "IC2") (pin "13") (pinfunction "(MISO)PB3_13") (pintype "bidirectional"))
    )
    (net (code "78") (name "unconnected-(IC2-(OC0)PB4-Pad14)") (class "Default")
      (node (ref "IC2") (pin "14") (pinfunction "(OC0)PB4_14") (pintype "bidirectional"))
    )
    (net (code "79") (name "unconnected-(IC2-(OC1B)PB6-Pad16)") (class "Default")
      (node (ref "IC2") (pin "16") (pinfunction "(OC1B)PB6_16") (pintype "bidirectional"))
    )
    (net (code "80") (name "unconnected-(IC2-(OC2{slash}OC1C)PB7-Pad17)") (class "Default")
      (node (ref "IC2") (pin "17") (pinfunction "(OC2/OC1C)PB7_17") (pintype "bidirectional"))
    )
    (net (code "81") (name "unconnected-(IC2-(OC3A{slash}AIN1)PE3-Pad5)") (class "Default")
      (node (ref "IC2") (pin "5") (pinfunction "(OC3A/AIN1)PE3_5") (pintype "bidirectional"))
    )
    (net (code "82") (name "unconnected-(IC2-(OC3C{slash}INT5)PE5-Pad7)") (class "Default")
      (node (ref "IC2") (pin "7") (pinfunction "(OC3C/INT5)PE5_7") (pintype "bidirectional"))
    )
    (net (code "83") (name "unconnected-(IC2-(SS)PB0-Pad10)") (class "Default")
      (node (ref "IC2") (pin "10") (pinfunction "(SS)PB0_10") (pintype "bidirectional"))
    )
    (net (code "84") (name "unconnected-(IC2-(T1)PD6-Pad31)") (class "Default")
      (node (ref "IC2") (pin "31") (pinfunction "(T1)PD6_31") (pintype "bidirectional"))
    )
    (net (code "85") (name "unconnected-(IC2-(T3{slash}INT6)PE6-Pad8)") (class "Default")
      (node (ref "IC2") (pin "8") (pinfunction "(T3/INT6)PE6_8") (pintype "bidirectional"))
    )
    (net (code "86") (name "unconnected-(IC2-(XCK0{slash}AIN0)PE2-Pad4)") (class "Default")
      (node (ref "IC2") (pin "4") (pinfunction "(XCK0/AIN0)PE2_4") (pintype "bidirectional"))
    )
    (net (code "87") (name "unconnected-(IC2-(XCK1)PD5-Pad30)") (class "Default")
      (node (ref "IC2") (pin "30") (pinfunction "(XCK1)PD5_30") (pintype "bidirectional"))
    )
    (net (code "88") (name "unconnected-(IC2-PEN-Pad1)") (class "Default")
      (node (ref "IC2") (pin "1") (pinfunction "PEN_1") (pintype "input"))
    )
    (net (code "89") (name "unconnected-(IC2-PF2(ADC2)-Pad59)") (class "Default")
      (node (ref "IC2") (pin "59") (pinfunction "PF2(ADC2)_59") (pintype "input"))
    )
    (net (code "90") (name "unconnected-(IC2-PF3(ADC3)-Pad58)") (class "Default")
      (node (ref "IC2") (pin "58") (pinfunction "PF3(ADC3)_58") (pintype "input"))
    )
    (net (code "91") (name "unconnected-(IC2-PF4(ADC4{slash}TCK)-Pad57)") (class "Default")
      (node (ref "IC2") (pin "57") (pinfunction "PF4(ADC4/TCK)_57") (pintype "input"))
    )
    (net (code "92") (name "unconnected-(IC2-PG0(WR)-Pad33)") (class "Default")
      (node (ref "IC2") (pin "33") (pinfunction "PG0(WR)_33") (pintype "bidirectional"))
    )
    (net (code "93") (name "unconnected-(IC2-PG1(RD)-Pad34)") (class "Default")
      (node (ref "IC2") (pin "34") (pinfunction "PG1(RD)_34") (pintype "bidirectional"))
    )
    (net (code "94") (name "unconnected-(IC2-PG2(ALE)-Pad43)") (class "Default")
      (node (ref "IC2") (pin "43") (pinfunction "PG2(ALE)_43") (pintype "bidirectional"))
    )
    (net (code "95") (name "unconnected-(SENSOR1-PadNC1)") (class "Default")
      (node (ref "SENSOR1") (pin "NC1") (pinfunction "NC1_NC1") (pintype "bidirectional"))
    )
    (net (code "96") (name "unconnected-(SENSOR1-PadNC2)") (class "Default")
      (node (ref "SENSOR1") (pin "NC2") (pinfunction "NC2_NC2") (pintype "bidirectional"))
    )
    (net (code "97") (name "unconnected-(SV1-Pad3)") (class "Default")
      (node (ref "SV1") (pin "3") (pinfunction "3_3") (pintype "passive"))
    )
    (net (code "98") (name "unconnected-(U$2-USBID-PadID)") (class "Default")
      (node (ref "U$2") (pin "ID") (pinfunction "USBID_ID") (pintype "bidirectional"))
    )
    (net (code "99") (name "unconnected-(U1-CTS-Pad11)") (class "Default")
      (node (ref "U1") (pin "11") (pinfunction "CTS_11") (pintype "input"))
    )
    (net (code "100") (name "unconnected-(U1-DCD-Pad10)") (class "Default")
      (node (ref "U1") (pin "10") (pinfunction "DCD_10") (pintype "input"))
    )
    (net (code "101") (name "unconnected-(U1-DSR-Pad9)") (class "Default")
      (node (ref "U1") (pin "9") (pinfunction "DSR_9") (pintype "input"))
    )
    (net (code "102") (name "unconnected-(U1-OSCI-Pad27)") (class "Default")
      (node (ref "U1") (pin "27") (pinfunction "OSCI_27") (pintype "input"))
    )
    (net (code "103") (name "unconnected-(U1-OSCO-Pad28)") (class "Default")
      (node (ref "U1") (pin "28") (pinfunction "OSCO_28") (pintype "output"))
    )
    (net (code "104") (name "unconnected-(U1-PWREN-Pad14)") (class "Default")
      (node (ref "U1") (pin "14") (pinfunction "PWREN_14") (pintype "input"))
    )
    (net (code "105") (name "unconnected-(U1-RESET-Pad19)") (class "Default")
      (node (ref "U1") (pin "19") (pinfunction "RESET_19") (pintype "input"))
    )
    (net (code "106") (name "unconnected-(U1-RI-Pad6)") (class "Default")
      (node (ref "U1") (pin "6") (pinfunction "RI_6") (pintype "input"))
    )
    (net (code "107") (name "unconnected-(U1-SLEEP-Pad12)") (class "Default")
      (node (ref "U1") (pin "12") (pinfunction "SLEEP_12") (pintype "input"))
    )
    (net (code "108") (name "unconnected-(U1-TXDEN-Pad13)") (class "Default")
      (node (ref "U1") (pin "13") (pinfunction "TXDEN_13") (pintype "input"))
    )
    (net (code "109") (name "unconnected-(WLAN1-PadGPIO0)") (class "Default")
      (node (ref "WLAN1") (pin "GPIO0") (pinfunction "GPIO0_GPIO0") (pintype "bidirectional"))
    )
    (net (code "110") (name "unconnected-(WLAN1-PadGPIO2)") (class "Default")
      (node (ref "WLAN1") (pin "GPIO2") (pinfunction "GPIO2_GPIO2") (pintype "bidirectional"))
    )
    (net (code "111") (name "unconnected-(WLAN1-PadGPIO12)") (class "Default")
      (node (ref "WLAN1") (pin "GPIO12") (pinfunction "GPIO12_GPIO12") (pintype "bidirectional"))
    )
    (net (code "112") (name "unconnected-(WLAN1-PadGPIO13)") (class "Default")
      (node (ref "WLAN1") (pin "GPIO13") (pinfunction "GPIO13_GPIO13") (pintype "bidirectional"))
    )
    (net (code "113") (name "unconnected-(WLAN1-PadGPIO14)") (class "Default")
      (node (ref "WLAN1") (pin "GPIO14") (pinfunction "GPIO14_GPIO14") (pintype "bidirectional"))
    )
    (net (code "114") (name "unconnected-(WLAN1-PadGPIO16)") (class "Default")
      (node (ref "WLAN1") (pin "GPIO16") (pinfunction "GPIO16_GPIO16") (pintype "bidirectional"))
    )
    (net (code "115") (name "unconnected-(WLAN1-PadNC)") (class "Default")
      (node (ref "WLAN1") (pin "NC") (pinfunction "NC_NC") (pintype "bidirectional"))
    )
  )
)
